# control_2.net
KiCad netlist of a schematic drawn in Altium Designer
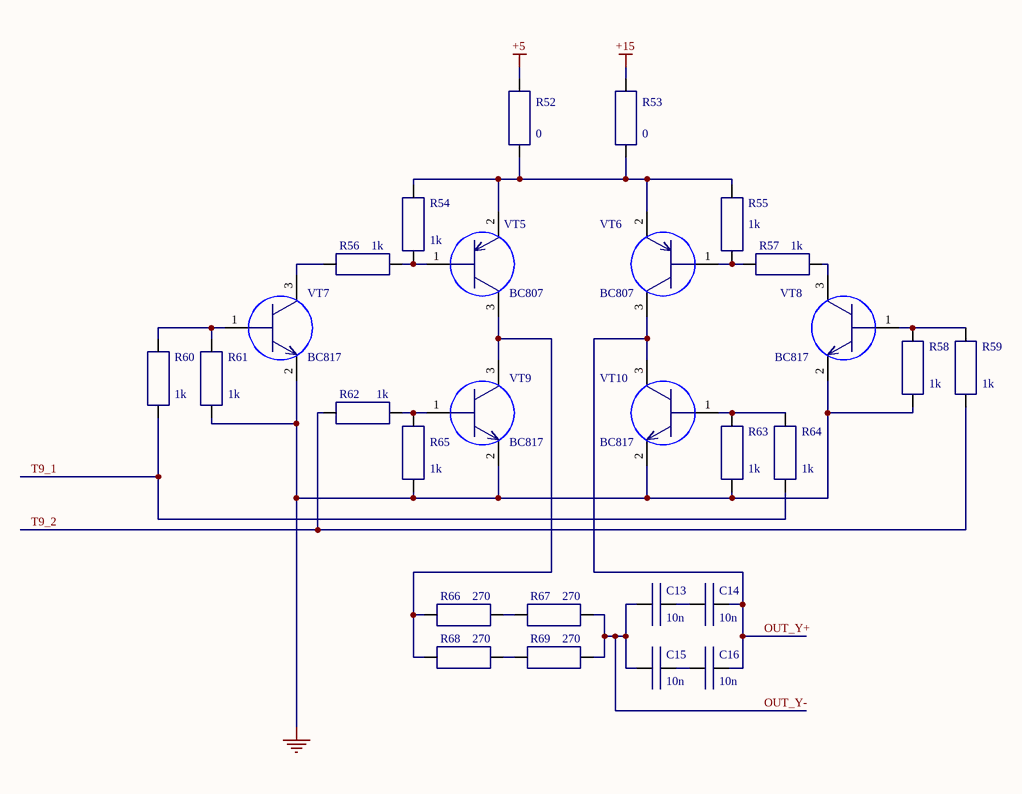
[diagram p0: control_2.SchDoc]

(export (version "E")
  (design (tool "Eeschema 10.0.6"))
  (components
    (comp (ref "C13") (value "10n") (footprint "C0805") (libsource (lib "Library") (part "C0805")))
    (comp (ref "C14") (value "10n") (footprint "C0805") (libsource (lib "Library") (part "C0805")))
    (comp (ref "C15") (value "10n") (footprint "C0805") (libsource (lib "Library") (part "C0805")))
    (comp (ref "C16") (value "10n") (footprint "C0805") (libsource (lib "Library") (part "C0805")))
    (comp (ref "R52") (value "0") (footprint "R1206") (libsource (lib "Library") (part "R1206")))
    (comp (ref "R53") (value "0") (footprint "R1206") (libsource (lib "Library") (part "R1206")))
    (comp (ref "R54") (value "1k") (footprint "R0805") (libsource (lib "Library") (part "R0805")))
    (comp (ref "R55") (value "1k") (footprint "R0805") (libsource (lib "Library") (part "R0805")))
    (comp (ref "R56") (value "1k") (footprint "R0805") (libsource (lib "Library") (part "R0805")))
    (comp (ref "R57") (value "1k") (footprint "R0805") (libsource (lib "Library") (part "R0805")))
    (comp (ref "R58") (value "1k") (footprint "R0805") (libsource (lib "Library") (part "R0805")))
    (comp (ref "R59") (value "1k") (footprint "R0805") (libsource (lib "Library") (part "R0805")))
    (comp (ref "R60") (value "1k") (footprint "R0805") (libsource (lib "Library") (part "R0805")))
    (comp (ref "R61") (value "1k") (footprint "R0805") (libsource (lib "Library") (part "R0805")))
    (comp (ref "R62") (value "1k") (footprint "R0805") (libsource (lib "Library") (part "R0805")))
    (comp (ref "R63") (value "1k") (footprint "R0805") (libsource (lib "Library") (part "R0805")))
    (comp (ref "R64") (value "1k") (footprint "R0805") (libsource (lib "Library") (part "R0805")))
    (comp (ref "R65") (value "1k") (footprint "R0805") (libsource (lib "Library") (part "R0805")))
    (comp (ref "R66") (value "270") (footprint "R1206") (libsource (lib "Library") (part "R1206")))
    (comp (ref "R67") (value "270") (footprint "R1206") (libsource (lib "Library") (part "R1206")))
    (comp (ref "R68") (value "270") (footprint "R1206") (libsource (lib "Library") (part "R1206")))
    (comp (ref "R69") (value "270") (footprint "R1206") (libsource (lib "Library") (part "R1206")))
    (comp (ref "VT5") (value "BC807") (footprint "SOT-23") (libsource (lib "Library") (part "PNP")))
    (comp (ref "VT6") (value "BC807") (footprint "SOT-23") (libsource (lib "Library") (part "PNP")))
    (comp (ref "VT7") (value "BC817") (footprint "SOT-23") (libsource (lib "Library") (part "NPN")))
    (comp (ref "VT8") (value "BC817") (footprint "SOT-23") (libsource (lib "Library") (part "NPN")))
    (comp (ref "VT9") (value "BC817") (footprint "SOT-23") (libsource (lib "Library") (part "NPN")))
    (comp (ref "VT10") (value "BC817") (footprint "SOT-23") (libsource (lib "Library") (part "NPN")))
  )
  (nets
    (net (code "1") (name "+5") (class "Default")
      (node (ref "R52") (pin "2") (pinfunction "2_2") (pintype "passive"))
    )
    (net (code "2") (name "+15") (class "Default")
      (node (ref "R53") (pin "2") (pinfunction "2_2") (pintype "passive"))
    )
    (net (code "3") (name "/OUT_Y+") (class "Default")
      (node (ref "C14") (pin "1") (pinfunction "1_1") (pintype "passive"))
      (node (ref "C16") (pin "1") (pinfunction "1_1") (pintype "passive"))
      (node (ref "VT10") (pin "3") (pinfunction "3_3") (pintype "passive"))
      (node (ref "VT6") (pin "3") (pinfunction "3_3") (pintype "passive"))
    )
    (net (code "4") (name "/OUT_Y-") (class "Default")
      (node (ref "C13") (pin "2") (pinfunction "2_2") (pintype "passive"))
      (node (ref "C15") (pin "2") (pinfunction "2_2") (pintype "passive"))
      (node (ref "R67") (pin "1") (pinfunction "1_1") (pintype "passive"))
      (node (ref "R69") (pin "1") (pinfunction "1_1") (pintype "passive"))
    )
    (net (code "5") (name "/T9_1") (class "Default")
      (node (ref "R60") (pin "1") (pinfunction "1_1") (pintype "passive"))
      (node (ref "R64") (pin "1") (pinfunction "1_1") (pintype "passive"))
    )
    (net (code "6") (name "/T9_2") (class "Default")
      (node (ref "R59") (pin "1") (pinfunction "1_1") (pintype "passive"))
      (node (ref "R62") (pin "2") (pinfunction "2_2") (pintype "passive"))
    )
    (net (code "7") (name "GND") (class "Default")
      (node (ref "R58") (pin "1") (pinfunction "1_1") (pintype "passive"))
      (node (ref "R61") (pin "1") (pinfunction "1_1") (pintype "passive"))
      (node (ref "R63") (pin "1") (pinfunction "1_1") (pintype "passive"))
      (node (ref "R65") (pin "1") (pinfunction "1_1") (pintype "passive"))
      (node (ref "VT10") (pin "2") (pinfunction "2_2") (pintype "passive"))
      (node (ref "VT7") (pin "2") (pinfunction "2_2") (pintype "passive"))
      (node (ref "VT8") (pin "2") (pinfunction "2_2") (pintype "passive"))
      (node (ref "VT9") (pin "2") (pinfunction "2_2") (pintype "passive"))
    )
    (net (code "8") (name "Net-(C13-Pad1)") (class "Default")
      (node (ref "C13") (pin "1") (pinfunction "1_1") (pintype "passive"))
      (node (ref "C14") (pin "2") (pinfunction "2_2") (pintype "passive"))
    )
    (net (code "9") (name "Net-(C15-Pad1)") (class "Default")
      (node (ref "C15") (pin "1") (pinfunction "1_1") (pintype "passive"))
      (node (ref "C16") (pin "2") (pinfunction "2_2") (pintype "passive"))
    )
    (net (code "10") (name "Net-(R52-Pad1)") (class "Default")
      (node (ref "R52") (pin "1") (pinfunction "1_1") (pintype "passive"))
      (node (ref "R53") (pin "1") (pinfunction "1_1") (pintype "passive"))
      (node (ref "R54") (pin "2") (pinfunction "2_2") (pintype "passive"))
      (node (ref "R55") (pin "2") (pinfunction "2_2") (pintype "passive"))
      (node (ref "VT5") (pin "2") (pinfunction "2_2") (pintype "passive"))
      (node (ref "VT6") (pin "2") (pinfunction "2_2") (pintype "passive"))
    )
    (net (code "11") (name "Net-(R54-Pad1)") (class "Default")
      (node (ref "R54") (pin "1") (pinfunction "1_1") (pintype "passive"))
      (node (ref "R56") (pin "1") (pinfunction "1_1") (pintype "passive"))
      (node (ref "VT5") (pin "1") (pinfunction "1_1") (pintype "passive"))
    )
    (net (code "12") (name "Net-(R55-Pad1)") (class "Default")
      (node (ref "R55") (pin "1") (pinfunction "1_1") (pintype "passive"))
      (node (ref "R57") (pin "2") (pinfunction "2_2") (pintype "passive"))
      (node (ref "VT6") (pin "1") (pinfunction "1_1") (pintype "passive"))
    )
    (net (code "13") (name "Net-(R56-Pad2)") (class "Default")
      (node (ref "R56") (pin "2") (pinfunction "2_2") (pintype "passive"))
      (node (ref "VT7") (pin "3") (pinfunction "3_3") (pintype "passive"))
    )
    (net (code "14") (name "Net-(R57-Pad1)") (class "Default")
      (node (ref "R57") (pin "1") (pinfunction "1_1") (pintype "passive"))
      (node (ref "VT8") (pin "3") (pinfunction "3_3") (pintype "passive"))
    )
    (net (code "15") (name "Net-(R58-Pad2)") (class "Default")
      (node (ref "R58") (pin "2") (pinfunction "2_2") (pintype "passive"))
      (node (ref "R59") (pin "2") (pinfunction "2_2") (pintype "passive"))
      (node (ref "VT8") (pin "1") (pinfunction "1_1") (pintype "passive"))
    )
    (net (code "16") (name "Net-(R60-Pad2)") (class "Default")
      (node (ref "R60") (pin "2") (pinfunction "2_2") (pintype "passive"))
      (node (ref "R61") (pin "2") (pinfunction "2_2") (pintype "passive"))
      (node (ref "VT7") (pin "1") (pinfunction "1_1") (pintype "passive"))
    )
    (net (code "17") (name "Net-(R62-Pad1)") (class "Default")
      (node (ref "R62") (pin "1") (pinfunction "1_1") (pintype "passive"))
      (node (ref "R65") (pin "2") (pinfunction "2_2") (pintype "passive"))
      (node (ref "VT9") (pin "1") (pinfunction "1_1") (pintype "passive"))
    )
    (net (code "18") (name "Net-(R63-Pad2)") (class "Default")
      (node (ref "R63") (pin "2") (pinfunction "2_2") (pintype "passive"))
      (node (ref "R64") (pin "2") (pinfunction "2_2") (pintype "passive"))
      (node (ref "VT10") (pin "1") (pinfunction "1_1") (pintype "passive"))
    )
    (net (code "19") (name "Net-(R66-Pad1)") (class "Default")
      (node (ref "R66") (pin "1") (pinfunction "1_1") (pintype "passive"))
      (node (ref "R67") (pin "2") (pinfunction "2_2") (pintype "passive"))
    )
    (net (code "20") (name "Net-(R66-Pad2)") (class "Default")
      (node (ref "R66") (pin "2") (pinfunction "2_2") (pintype "passive"))
      (node (ref "R68") (pin "2") (pinfunction "2_2") (pintype "passive"))
      (node (ref "VT5") (pin "3") (pinfunction "3_3") (pintype "passive"))
      (node (ref "VT9") (pin "3") (pinfunction "3_3") (pintype "passive"))
    )
    (net (code "21") (name "Net-(R68-Pad1)") (class "Default")
      (node (ref "R68") (pin "1") (pinfunction "1_1") (pintype "passive"))
      (node (ref "R69") (pin "2") (pinfunction "2_2") (pintype "passive"))
    )
  )
)
